# power.net
KiCad netlist of a schematic drawn in Altium Designer
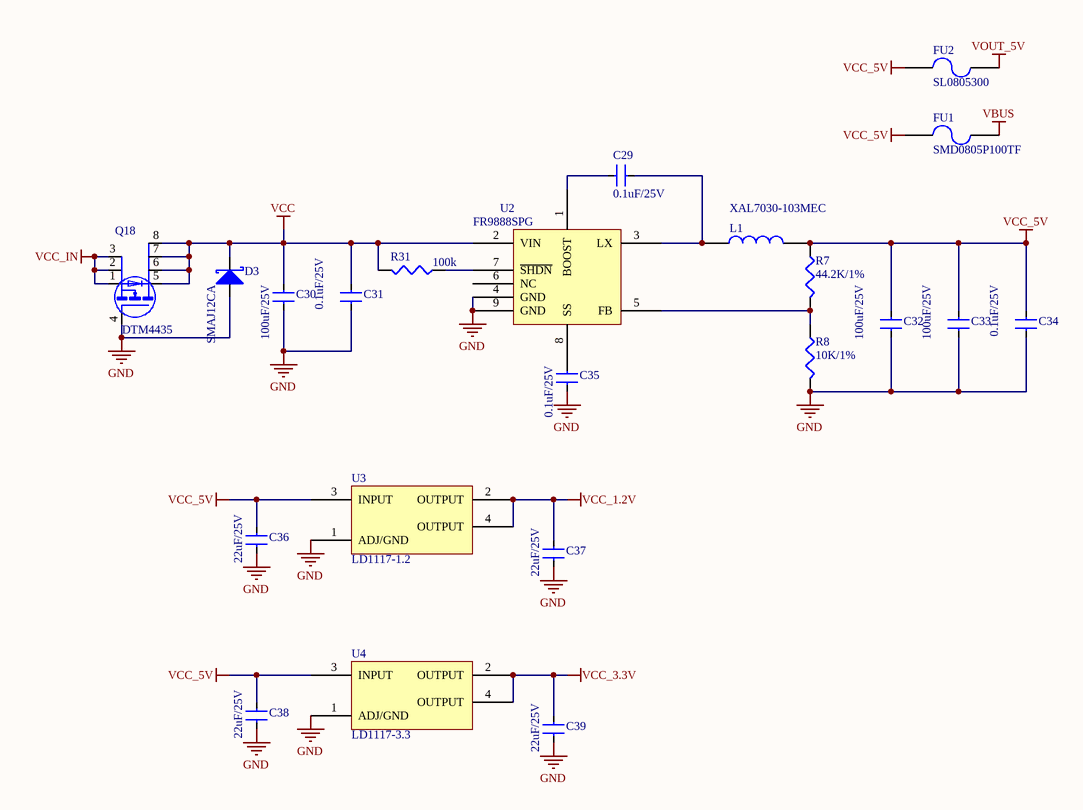
[diagram p0: power.SchDoc]

(export (version "E")
  (design (tool "Eeschema 10.0.6"))
  (components
    (comp (ref "C29")
      (value "0.1uF/25V")
      (footprint "0603C")
      (description "CCX85-103")
      (libsource (lib "无极性电容") (part "0.01UF"))
    )
    (comp (ref "C30")
      (value "100uF/25V")
      (footprint "1210C")
      (description "CCX85-103")
      (libsource (lib "无极性电容") (part "0.01UF"))
    )
    (comp (ref "C31")
      (value "0.1uF/25V")
      (footprint "0603C")
      (description "CCX85-103")
      (libsource (lib "无极性电容") (part "0.01UF"))
    )
    (comp (ref "C32")
      (value "100uF/25V")
      (footprint "1210C")
      (description "CCX85-103")
      (libsource (lib "无极性电容") (part "0.01UF"))
    )
    (comp (ref "C33")
      (value "100uF/25V")
      (footprint "1210C")
      (description "CCX85-103")
      (libsource (lib "无极性电容") (part "0.01UF"))
    )
    (comp (ref "C34")
      (value "0.1uF/25V")
      (footprint "0603C")
      (description "CCX85-103")
      (libsource (lib "无极性电容") (part "0.01UF"))
    )
    (comp (ref "C35")
      (value "0.1uF/25V")
      (footprint "0603C")
      (description "CCX85-103")
      (libsource (lib "无极性电容") (part "0.01UF"))
    )
    (comp (ref "C36")
      (value "22uF/25V")
      (footprint "1210C")
      (description "CCX85-103")
      (libsource (lib "无极性电容") (part "0.01UF"))
    )
    (comp (ref "C37")
      (value "22uF/25V")
      (footprint "1210C")
      (description "CCX85-103")
      (libsource (lib "无极性电容") (part "0.01UF"))
    )
    (comp (ref "C38")
      (value "22uF/25V")
      (footprint "1210C")
      (description "CCX85-103")
      (libsource (lib "无极性电容") (part "0.01UF"))
    )
    (comp (ref "C39")
      (value "22uF/25V")
      (footprint "1210C")
      (description "CCX85-103")
      (libsource (lib "无极性电容") (part "0.01UF"))
    )
    (comp (ref "D3")
      (value "SMAJ12CA")
      (footprint "SMA")
      (description "Schottky Diode")
      (libsource (lib "*") (part "DIODE S"))
    )
    (comp (ref "FU1")
      (value "SMD0805P100TF")
      (footprint "F0805")
      (description "Fuse")
      (libsource (lib "SM") (part "FUSE2"))
    )
    (comp (ref "FU2")
      (value "SL0805300")
      (footprint "F0805")
      (description "Fuse")
      (libsource (lib "SM") (part "FUSE2"))
    )
    (comp (ref "L1") (value "XAL7030-103MEC") (footprint "XAL7030") (libsource (lib "*") (part "INDUCTOR")))
    (comp (ref "Q18")
      (value "DTM4435")
      (footprint "SO-8")
      (description "Si4004DY")
      (libsource (lib "Schlib_20110825") (part "Si4004DY"))
    )
    (comp (ref "R7")
      (value "44.2K/1%")
      (footprint "0603R")
      (description "Resistor")
      (fields (field (name "PUBLISHER") "Altium Limited"))
      (libsource (lib "SM") (part "Res3"))
    )
    (comp (ref "R8")
      (value "10K/1%")
      (footprint "0603R")
      (description "Resistor")
      (fields (field (name "PUBLISHER") "Altium Limited"))
      (libsource (lib "SM") (part "Res3"))
    )
    (comp (ref "R31")
      (value "100k")
      (footprint "0603R")
      (description "Resistor")
      (fields (field (name "PUBLISHER") "Altium Limited"))
      (libsource (lib "SM") (part "Res3"))
    )
    (comp (ref "U2")
      (value "FR9888SPG")
      (footprint "SOP120P600-8N")
      (libsource (lib "stm32") (part "FR9888SPG"))
    )
    (comp (ref "U3") (value "LD1117-1.2") (footprint "sot223") (libsource (lib "stm32") (part "LD1117-1.2")))
    (comp (ref "U4") (value "LD1117-3.3") (footprint "sot223") (libsource (lib "stm32") (part "LD1117-1.2")))
  )
  (nets
    (net (code "1") (name "GND") (class "Default")
      (node (ref "C30") (pin "2") (pinfunction "2_2") (pintype "passive"))
      (node (ref "C31") (pin "2") (pinfunction "2_2") (pintype "passive"))
      (node (ref "C32") (pin "2") (pinfunction "2_2") (pintype "passive"))
      (node (ref "C33") (pin "2") (pinfunction "2_2") (pintype "passive"))
      (node (ref "C34") (pin "2") (pinfunction "2_2") (pintype "passive"))
      (node (ref "C35") (pin "2") (pinfunction "2_2") (pintype "passive"))
      (node (ref "C36") (pin "2") (pinfunction "2_2") (pintype "passive"))
      (node (ref "C37") (pin "2") (pinfunction "2_2") (pintype "passive"))
      (node (ref "C38") (pin "2") (pinfunction "2_2") (pintype "passive"))
      (node (ref "C39") (pin "2") (pinfunction "2_2") (pintype "passive"))
      (node (ref "D3") (pin "1") (pinfunction "A_1") (pintype "passive"))
      (node (ref "Q18") (pin "4") (pinfunction "G_4") (pintype "passive"))
      (node (ref "R8") (pin "2") (pinfunction "2_2") (pintype "passive"))
      (node (ref "U2") (pin "4") (pinfunction "GND_4") (pintype "passive"))
      (node (ref "U2") (pin "9") (pinfunction "GND_9") (pintype "passive"))
      (node (ref "U3") (pin "1") (pinfunction "ADJ/GND_1") (pintype "passive"))
      (node (ref "U4") (pin "1") (pinfunction "ADJ/GND_1") (pintype "passive"))
    )
    (net (code "2") (name "Net-(U2-BOOST)") (class "Default")
      (node (ref "C29") (pin "1") (pinfunction "1_1") (pintype "passive"))
      (node (ref "U2") (pin "1") (pinfunction "BOOST_1") (pintype "passive"))
    )
    (net (code "3") (name "Net-(U2-FB)") (class "Default")
      (node (ref "R7") (pin "2") (pinfunction "2_2") (pintype "passive"))
      (node (ref "R8") (pin "1") (pinfunction "1_1") (pintype "passive"))
      (node (ref "U2") (pin "5") (pinfunction "FB_5") (pintype "passive"))
    )
    (net (code "4") (name "Net-(U2-LX)") (class "Default")
      (node (ref "C29") (pin "2") (pinfunction "2_2") (pintype "passive"))
      (node (ref "L1") (pin "1") (pinfunction "1_1") (pintype "passive"))
      (node (ref "U2") (pin "3") (pinfunction "LX_3") (pintype "passive"))
    )
    (net (code "5") (name "Net-(U2-SS)") (class "Default")
      (node (ref "C35") (pin "1") (pinfunction "1_1") (pintype "passive"))
      (node (ref "U2") (pin "8") (pinfunction "SS_8") (pintype "passive"))
    )
    (net (code "6") (name "Net-(U2-~{SHDN})") (class "Default")
      (node (ref "R31") (pin "1") (pinfunction "1_1") (pintype "passive"))
      (node (ref "U2") (pin "7") (pinfunction "~{SHDN}_7") (pintype "passive"))
    )
    (net (code "7") (name "VBUS") (class "Default")
      (node (ref "FU1") (pin "2") (pinfunction "2_2") (pintype "passive"))
    )
    (net (code "8") (name "VCC") (class "Default")
      (node (ref "C30") (pin "1") (pinfunction "1_1") (pintype "passive"))
      (node (ref "C31") (pin "1") (pinfunction "1_1") (pintype "passive"))
      (node (ref "D3") (pin "2") (pinfunction "K_2") (pintype "passive"))
      (node (ref "Q18") (pin "5") (pinfunction "D_5") (pintype "passive"))
      (node (ref "Q18") (pin "6") (pinfunction "D_6") (pintype "passive"))
      (node (ref "Q18") (pin "7") (pinfunction "D_7") (pintype "passive"))
      (node (ref "Q18") (pin "8") (pinfunction "D_8") (pintype "passive"))
      (node (ref "R31") (pin "2") (pinfunction "2_2") (pintype "passive"))
      (node (ref "U2") (pin "2") (pinfunction "VIN_2") (pintype "passive"))
    )
    (net (code "9") (name "VCC_1.2V") (class "Default")
      (node (ref "C37") (pin "1") (pinfunction "1_1") (pintype "passive"))
      (node (ref "U3") (pin "2") (pinfunction "OUTPUT_2") (pintype "passive"))
      (node (ref "U3") (pin "4") (pinfunction "OUTPUT_4") (pintype "passive"))
    )
    (net (code "10") (name "VCC_3.3V") (class "Default")
      (node (ref "C39") (pin "1") (pinfunction "1_1") (pintype "passive"))
      (node (ref "U4") (pin "2") (pinfunction "OUTPUT_2") (pintype "passive"))
      (node (ref "U4") (pin "4") (pinfunction "OUTPUT_4") (pintype "passive"))
    )
    (net (code "11") (name "VCC_5V") (class "Default")
      (node (ref "C32") (pin "1") (pinfunction "1_1") (pintype "passive"))
      (node (ref "C33") (pin "1") (pinfunction "1_1") (pintype "passive"))
      (node (ref "C34") (pin "1") (pinfunction "1_1") (pintype "passive"))
      (node (ref "C36") (pin "1") (pinfunction "1_1") (pintype "passive"))
      (node (ref "C38") (pin "1") (pinfunction "1_1") (pintype "passive"))
      (node (ref "FU1") (pin "1") (pinfunction "1_1") (pintype "passive"))
      (node (ref "FU2") (pin "1") (pinfunction "1_1") (pintype "passive"))
      (node (ref "L1") (pin "2") (pinfunction "2_2") (pintype "passive"))
      (node (ref "R7") (pin "1") (pinfunction "1_1") (pintype "passive"))
      (node (ref "U3") (pin "3") (pinfunction "INPUT_3") (pintype "passive"))
      (node (ref "U4") (pin "3") (pinfunction "INPUT_3") (pintype "passive"))
    )
    (net (code "12") (name "VCC_IN") (class "Default")
      (node (ref "Q18") (pin "1") (pinfunction "S_1") (pintype "passive"))
      (node (ref "Q18") (pin "2") (pinfunction "S_2") (pintype "passive"))
      (node (ref "Q18") (pin "3") (pinfunction "S_3") (pintype "passive"))
    )
    (net (code "13") (name "VOUT_5V") (class "Default")
      (node (ref "FU2") (pin "2") (pinfunction "2_2") (pintype "passive"))
    )
    (net (code "14") (name "unconnected-(U2-NC-Pad6)") (class "Default")
      (node (ref "U2") (pin "6") (pinfunction "NC_6") (pintype "passive"))
    )
  )
)
